# pcb.net
KiCad netlist of a schematic drawn in EAGLE
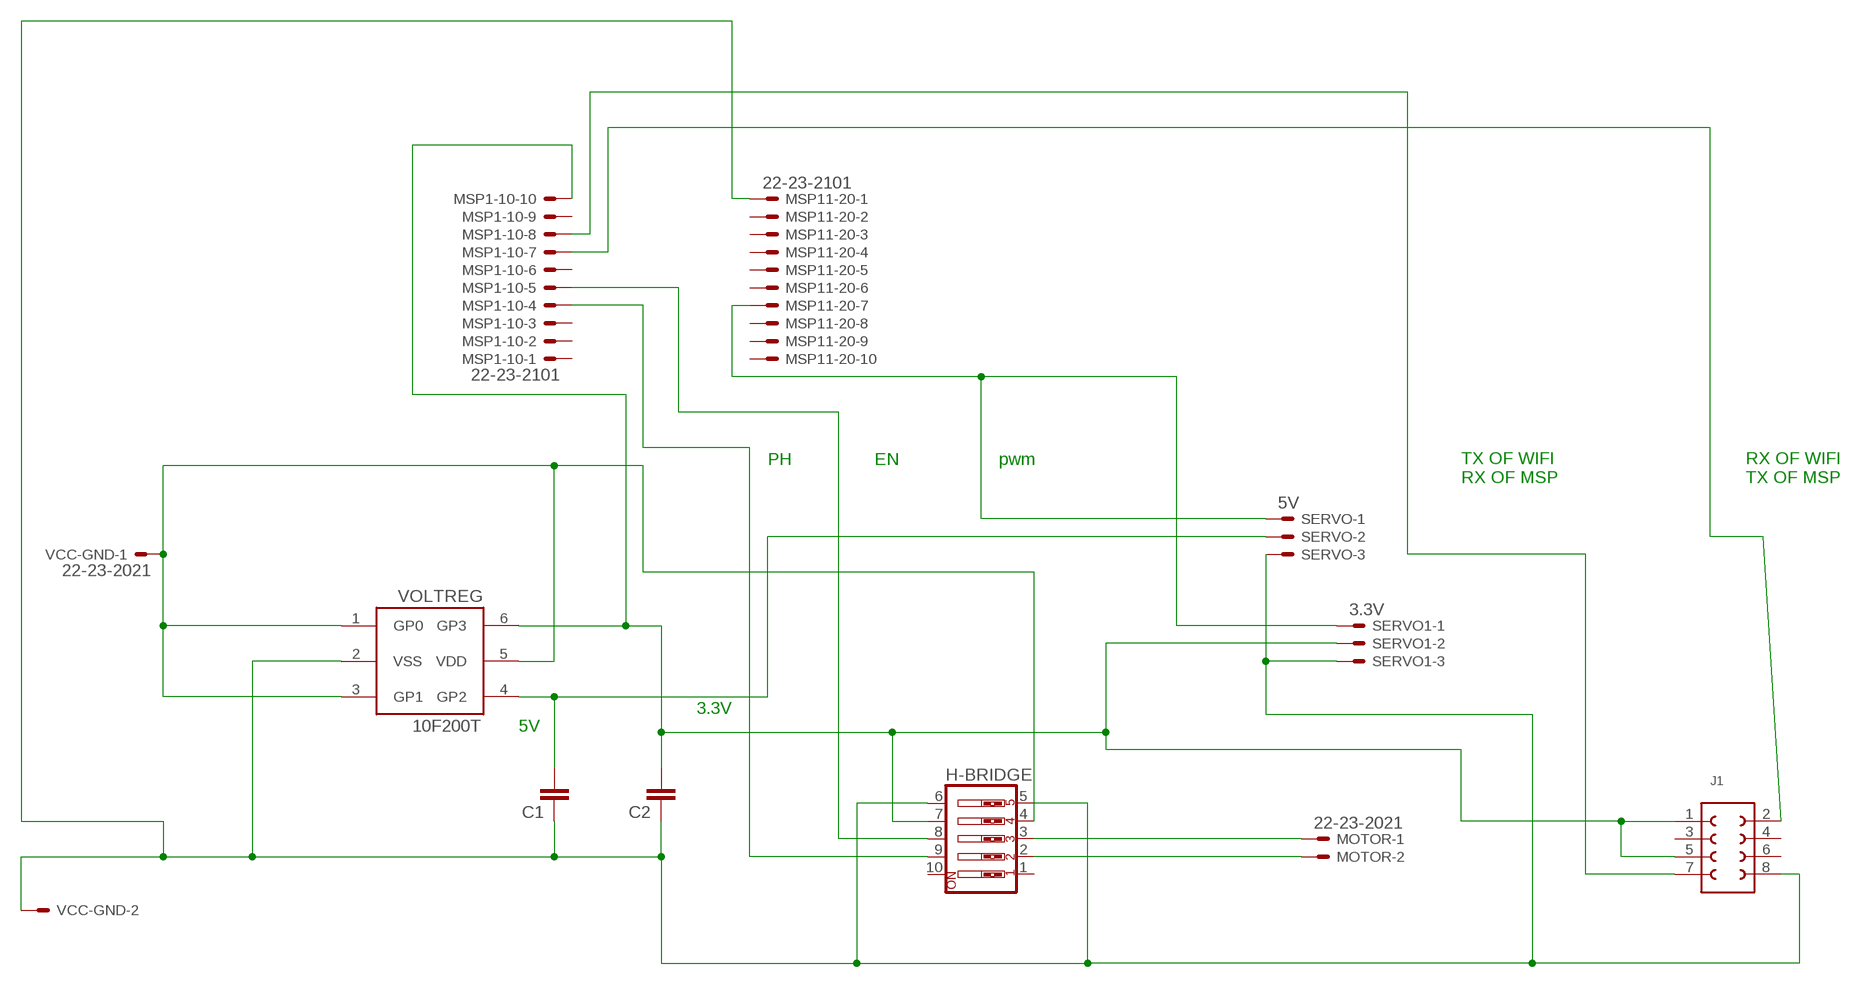
[diagram p0: schematic, sheet 1]

(export (version "E")
  (design (tool "Eeschema 10.0.6"))
  (components
    (comp (ref "C1")
      (value "C2,5-3")
      (footprint "eagle-import:C2.5-3")
      (libsource (lib "eagle-import") (part "C2,5-3"))
    )
    (comp (ref "C2")
      (value "C2,5-3")
      (footprint "eagle-import:C2.5-3")
      (libsource (lib "eagle-import") (part "C2,5-3"))
    )
    (comp (ref "H-BRIDGE")
      (value "SW_DIP-5")
      (footprint "eagle-import:EDG-05")
      (libsource (lib "eagle-import") (part "SW_DIP-5"))
    )
    (comp (ref "J1")
      (value "61300821121")
      (footprint "eagle-import:61300821121")
      (libsource (lib "eagle-import") (part "61300821121"))
    )
    (comp (ref "MOTOR")
      (value "22-23-2021")
      (footprint "eagle-import:22-23-2021")
      (fields (field (name "MF") "MOLEX"))
      (libsource (lib "eagle-import") (part "22-23-2021"))
    )
    (comp (ref "MSP1-10")
      (value "22-23-2101")
      (footprint "eagle-import:22-23-2101")
      (fields (field (name "MF") "MOLEX"))
      (libsource (lib "eagle-import") (part "22-23-2101"))
    )
    (comp (ref "MSP11-20")
      (value "22-23-2101")
      (footprint "eagle-import:22-23-2101")
      (fields (field (name "MF") "MOLEX"))
      (libsource (lib "eagle-import") (part "22-23-2101"))
    )
    (comp (ref "SERVO")
      (value "5V")
      (footprint "eagle-import:22-23-2031")
      (fields (field (name "MF") "MOLEX") (field (name "MPN") "22-23-2031"))
      (libsource (lib "eagle-import") (part "22-23-2031"))
    )
    (comp (ref "SERVO1")
      (value "3.3V")
      (footprint "eagle-import:22-23-2031")
      (fields (field (name "MF") "MOLEX") (field (name "MPN") "22-23-2031"))
      (libsource (lib "eagle-import") (part "22-23-2031"))
    )
    (comp (ref "VCC-GND")
      (value "22-23-2021")
      (footprint "eagle-import:22-23-2021")
      (fields (field (name "MF") "MOLEX"))
      (libsource (lib "eagle-import") (part "22-23-2021"))
    )
    (comp (ref "VOLTREG")
      (value "10F200T")
      (footprint "eagle-import:SOT23-6")
      (libsource (lib "eagle-import") (part "10F200T"))
    )
  )
  (nets
    (net (code "1") (name "Net-(J1-3)") (class "Default")
      (node (ref "C2") (pin "2") (pinfunction "2_2") (pintype "passive"))
      (node (ref "H-BRIDGE") (pin "7") (pinfunction "7_7") (pintype "passive"))
      (node (ref "J1") (pin "1") (pinfunction "1_1") (pintype "passive"))
      (node (ref "J1") (pin "5") (pinfunction "3_5") (pintype "passive"))
      (node (ref "MSP1-10") (pin "10") (pinfunction "S_10") (pintype "passive"))
      (node (ref "SERVO1") (pin "2") (pinfunction "S_2") (pintype "passive"))
      (node (ref "VOLTREG") (pin "6") (pinfunction "GP3_6") (pintype "bidirectional"))
    )
    (net (code "2") (name "Net-(J1-4)") (class "Default")
      (node (ref "J1") (pin "7") (pinfunction "4_7") (pintype "passive"))
      (node (ref "MSP1-10") (pin "8") (pinfunction "S_8") (pintype "passive"))
    )
    (net (code "3") (name "Net-(J1-5)") (class "Default")
      (node (ref "C1") (pin "1") (pinfunction "1_1") (pintype "passive"))
      (node (ref "C2") (pin "1") (pinfunction "1_1") (pintype "passive"))
      (node (ref "H-BRIDGE") (pin "5") (pinfunction "5_5") (pintype "passive"))
      (node (ref "H-BRIDGE") (pin "6") (pinfunction "6_6") (pintype "passive"))
      (node (ref "J1") (pin "8") (pinfunction "5_8") (pintype "passive"))
      (node (ref "MSP11-20") (pin "1") (pinfunction "S_1") (pintype "passive"))
      (node (ref "SERVO") (pin "3") (pinfunction "S_3") (pintype "passive"))
      (node (ref "SERVO1") (pin "3") (pinfunction "S_3") (pintype "passive"))
      (node (ref "VCC-GND") (pin "2") (pinfunction "S_2") (pintype "passive"))
      (node (ref "VOLTREG") (pin "2") (pinfunction "VSS_2") (pintype "power_in"))
    )
    (net (code "4") (name "Net-(J1-8)") (class "Default")
      (node (ref "J1") (pin "2") (pinfunction "8_2") (pintype "passive"))
      (node (ref "MSP1-10") (pin "7") (pinfunction "S_7") (pintype "passive"))
    )
    (net (code "5") (name "Net-(MOTORA-S)") (class "Default")
      (node (ref "H-BRIDGE") (pin "3") (pinfunction "3_3") (pintype "passive"))
      (node (ref "MOTOR") (pin "1") (pinfunction "S_1") (pintype "passive"))
    )
    (net (code "6") (name "Net-(MOTORB-S)") (class "Default")
      (node (ref "H-BRIDGE") (pin "2") (pinfunction "2_2") (pintype "passive"))
      (node (ref "MOTOR") (pin "2") (pinfunction "S_2") (pintype "passive"))
    )
    (net (code "7") (name "Net-(MSP1-10E-S)") (class "Default")
      (node (ref "H-BRIDGE") (pin "9") (pinfunction "9_9") (pintype "passive"))
      (node (ref "MSP1-10") (pin "4") (pinfunction "S_4") (pintype "passive"))
    )
    (net (code "8") (name "Net-(MSP1-10F-S)") (class "Default")
      (node (ref "H-BRIDGE") (pin "8") (pinfunction "8_8") (pintype "passive"))
      (node (ref "MSP1-10") (pin "5") (pinfunction "S_5") (pintype "passive"))
    )
    (net (code "9") (name "Net-(MSP11-20H-S)") (class "Default")
      (node (ref "MSP11-20") (pin "7") (pinfunction "S_7") (pintype "passive"))
      (node (ref "SERVO") (pin "1") (pinfunction "S_1") (pintype "passive"))
      (node (ref "SERVO1") (pin "1") (pinfunction "S_1") (pintype "passive"))
    )
    (net (code "10") (name "Net-(SERVOB-S)") (class "Default")
      (node (ref "C1") (pin "2") (pinfunction "2_2") (pintype "passive"))
      (node (ref "SERVO") (pin "2") (pinfunction "S_2") (pintype "passive"))
      (node (ref "VOLTREG") (pin "4") (pinfunction "GP2_4") (pintype "bidirectional"))
    )
    (net (code "11") (name "Net-(VCC-GNDA-S)") (class "Default")
      (node (ref "H-BRIDGE") (pin "4") (pinfunction "4_4") (pintype "passive"))
      (node (ref "VCC-GND") (pin "1") (pinfunction "S_1") (pintype "passive"))
      (node (ref "VOLTREG") (pin "1") (pinfunction "GP0_1") (pintype "bidirectional"))
      (node (ref "VOLTREG") (pin "3") (pinfunction "GP1_3") (pintype "bidirectional"))
      (node (ref "VOLTREG") (pin "5") (pinfunction "VDD_5") (pintype "power_in"))
    )
    (net (code "12") (name "unconnected-(H-BRIDGE-Pad1)") (class "Default")
      (node (ref "H-BRIDGE") (pin "1") (pinfunction "1_1") (pintype "passive"))
    )
    (net (code "13") (name "unconnected-(H-BRIDGE-Pad10)") (class "Default")
      (node (ref "H-BRIDGE") (pin "10") (pinfunction "10_10") (pintype "passive"))
    )
    (net (code "14") (name "unconnected-(J1-2-Pad3)") (class "Default")
      (node (ref "J1") (pin "3") (pinfunction "2_3") (pintype "passive"))
    )
    (net (code "15") (name "unconnected-(J1-7-Pad4)") (class "Default")
      (node (ref "J1") (pin "4") (pinfunction "7_4") (pintype "passive"))
    )
    (net (code "16") (name "unconnected-(J1-Pad6)") (class "Default")
      (node (ref "J1") (pin "6") (pinfunction "6_6") (pintype "passive"))
    )
    (net (code "17") (name "unconnected-(MSP1-10A-S-Pad1)") (class "Default")
      (node (ref "MSP1-10") (pin "1") (pinfunction "S_1") (pintype "passive"))
    )
    (net (code "18") (name "unconnected-(MSP1-10C-S-Pad2)") (class "Default")
      (node (ref "MSP1-10") (pin "2") (pinfunction "S_2") (pintype "passive"))
    )
    (net (code "19") (name "unconnected-(MSP1-10D-S-Pad3)") (class "Default")
      (node (ref "MSP1-10") (pin "3") (pinfunction "S_3") (pintype "passive"))
    )
    (net (code "20") (name "unconnected-(MSP1-10G-S-Pad6)") (class "Default")
      (node (ref "MSP1-10") (pin "6") (pinfunction "S_6") (pintype "passive"))
    )
    (net (code "21") (name "unconnected-(MSP1-10J-S-Pad9)") (class "Default")
      (node (ref "MSP1-10") (pin "9") (pinfunction "S_9") (pintype "passive"))
    )
    (net (code "22") (name "unconnected-(MSP11-20B-S-Pad10)") (class "Default")
      (node (ref "MSP11-20") (pin "10") (pinfunction "S_10") (pintype "passive"))
    )
    (net (code "23") (name "unconnected-(MSP11-20C-S-Pad2)") (class "Default")
      (node (ref "MSP11-20") (pin "2") (pinfunction "S_2") (pintype "passive"))
    )
    (net (code "24") (name "unconnected-(MSP11-20D-S-Pad3)") (class "Default")
      (node (ref "MSP11-20") (pin "3") (pinfunction "S_3") (pintype "passive"))
    )
    (net (code "25") (name "unconnected-(MSP11-20E-S-Pad4)") (class "Default")
      (node (ref "MSP11-20") (pin "4") (pinfunction "S_4") (pintype "passive"))
    )
    (net (code "26") (name "unconnected-(MSP11-20F-S-Pad5)") (class "Default")
      (node (ref "MSP11-20") (pin "5") (pinfunction "S_5") (pintype "passive"))
    )
    (net (code "27") (name "unconnected-(MSP11-20G-S-Pad6)") (class "Default")
      (node (ref "MSP11-20") (pin "6") (pinfunction "S_6") (pintype "passive"))
    )
    (net (code "28") (name "unconnected-(MSP11-20I-S-Pad8)") (class "Default")
      (node (ref "MSP11-20") (pin "8") (pinfunction "S_8") (pintype "passive"))
    )
    (net (code "29") (name "unconnected-(MSP11-20J-S-Pad9)") (class "Default")
      (node (ref "MSP11-20") (pin "9") (pinfunction "S_9") (pintype "passive"))
    )
  )
)
